# DMC.net
KiCad netlist of a schematic drawn in Altium Designer
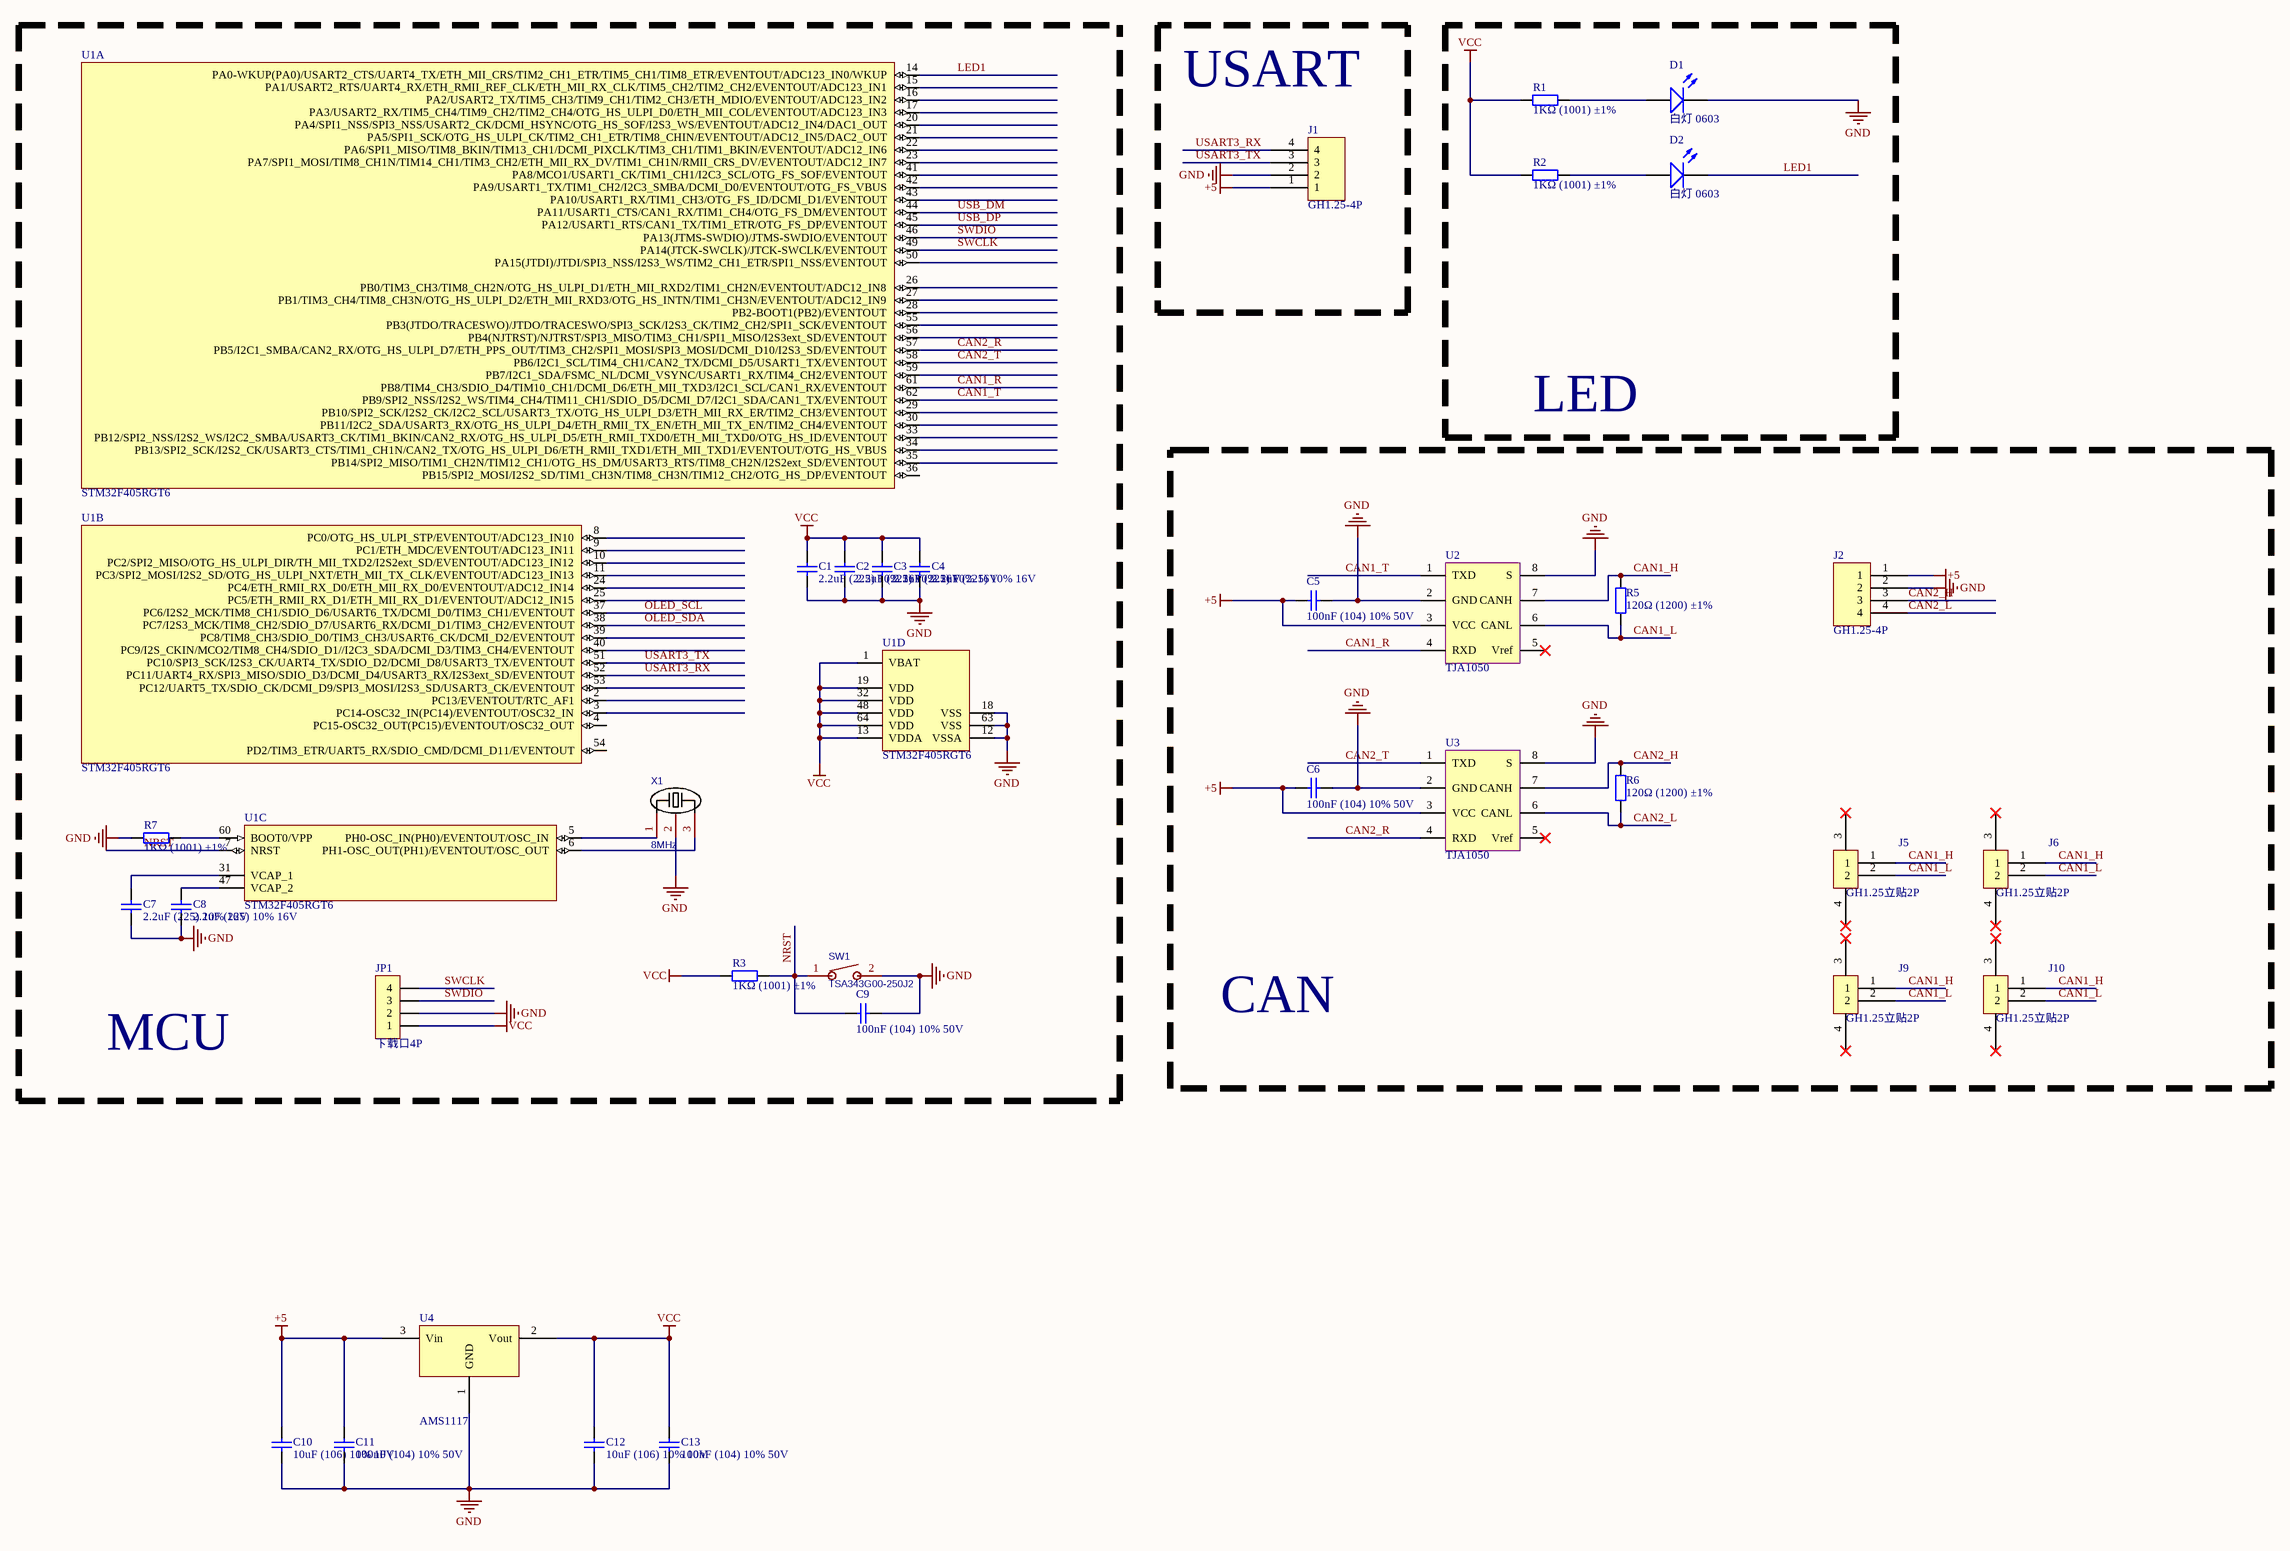
[diagram p0: DMC.SchDoc]

(export (version "E")
  (design (tool "Eeschema 10.0.6"))
  (components
    (comp (ref "C1")
      (value "2.2uF (225) 10% 16V")
      (footprint "0603_C")
      (description "贴片电容")
      (libsource (lib "Miscellaneous Devices LC") (part "0603 2.2uF (225) 10% 16V"))
    )
    (comp (ref "C2")
      (value "2.2uF (225) 10% 16V")
      (footprint "0603_C")
      (description "贴片电容")
      (libsource (lib "Miscellaneous Devices LC") (part "0603 2.2uF (225) 10% 16V"))
    )
    (comp (ref "C3")
      (value "2.2uF (225) 10% 16V")
      (footprint "0603_C")
      (description "贴片电容")
      (libsource (lib "Miscellaneous Devices LC") (part "0603 2.2uF (225) 10% 16V"))
    )
    (comp (ref "C4")
      (value "2.2uF (225) 10% 16V")
      (footprint "0603_C")
      (description "贴片电容")
      (libsource (lib "Miscellaneous Devices LC") (part "0603 2.2uF (225) 10% 16V"))
    )
    (comp (ref "C5")
      (value "100nF (104) 10% 50V")
      (footprint "0603_C")
      (description "贴片电容")
      (libsource (lib "Miscellaneous Devices LC") (part "0603 100nF (104) 10% 50V"))
    )
    (comp (ref "C6")
      (value "100nF (104) 10% 50V")
      (footprint "0603_C")
      (description "贴片电容")
      (libsource (lib "Miscellaneous Devices LC") (part "0603 100nF (104) 10% 50V"))
    )
    (comp (ref "C7")
      (value "2.2uF (225) 10% 16V")
      (footprint "0603_C")
      (description "贴片电容")
      (libsource (lib "Miscellaneous Devices LC") (part "0603 2.2uF (225) 10% 16V"))
    )
    (comp (ref "C8")
      (value "2.2uF (225) 10% 16V")
      (footprint "0603_C")
      (description "贴片电容")
      (libsource (lib "Miscellaneous Devices LC") (part "0603 2.2uF (225) 10% 16V"))
    )
    (comp (ref "C9")
      (value "100nF (104) 10% 50V")
      (footprint "0603_C")
      (description "贴片电容")
      (libsource (lib "Miscellaneous Devices LC") (part "0603 100nF (104) 10% 50V"))
    )
    (comp (ref "C10")
      (value "10uF (106) 10% 10V")
      (footprint "0603_C")
      (description "贴片电容")
      (libsource (lib "Miscellaneous Devices LC") (part "0603 10uF (106) 10% 10V"))
    )
    (comp (ref "C11")
      (value "100nF (104) 10% 50V")
      (footprint "0603_C")
      (description "贴片电容")
      (libsource (lib "Miscellaneous Devices LC") (part "0603 100nF (104) 10% 50V"))
    )
    (comp (ref "C12")
      (value "10uF (106) 10% 10V")
      (footprint "0603_C")
      (description "贴片电容")
      (libsource (lib "Miscellaneous Devices LC") (part "0603 10uF (106) 10% 10V"))
    )
    (comp (ref "C13")
      (value "100nF (104) 10% 50V")
      (footprint "0603_C")
      (description "贴片电容")
      (libsource (lib "Miscellaneous Devices LC") (part "0603 100nF (104) 10% 50V"))
    )
    (comp (ref "D1")
      (value "白灯 0603")
      (footprint "0603_LED_S1")
      (description "发光二极管")
      (libsource (lib "Miscellaneous Devices LC") (part "0603 白灯"))
    )
    (comp (ref "D2")
      (value "白灯 0603")
      (footprint "0603_LED_S1")
      (description "发光二极管")
      (libsource (lib "Miscellaneous Devices LC") (part "0603 白灯"))
    )
    (comp (ref "J1")
      (value "GH1.25-4P")
      (footprint "GH1.25-4P")
      (description "GH1.25-4P 卧")
      (libsource (lib "") (part "GH1.25-4P_1"))
    )
    (comp (ref "J2")
      (value "GH1.25-4P")
      (footprint "GH1.25-4P")
      (description "GH1.25-4P 卧")
      (libsource (lib "MyLib") (part "GH1.25-4P"))
    )
    (comp (ref "J5")
      (value "GH1.25立贴2P")
      (footprint "CONN-SMD_2P-V-P1.25-L_X1251WVS-02HF-LPSW")
      (libsource (lib "MyLib") (part "GH1.25立贴2P"))
    )
    (comp (ref "J6")
      (value "GH1.25立贴2P")
      (footprint "CONN-SMD_2P-V-P1.25-L_X1251WVS-02HF-LPSW")
      (libsource (lib "MyLib") (part "GH1.25立贴2P"))
    )
    (comp (ref "J9")
      (value "GH1.25立贴2P")
      (footprint "CONN-SMD_2P-V-P1.25-L_X1251WVS-02HF-LPSW")
      (libsource (lib "MyLib") (part "GH1.25立贴2P"))
    )
    (comp (ref "J10")
      (value "GH1.25立贴2P")
      (footprint "CONN-SMD_2P-V-P1.25-L_X1251WVS-02HF-LPSW")
      (libsource (lib "MyLib") (part "GH1.25立贴2P"))
    )
    (comp (ref "JP1")
      (value "下载口4P")
      (footprint "下载口4pin")
      (description "下载口4PIN SWD")
      (libsource (lib "0.0 - YltsSchlib") (part "接插件-下载口4P"))
    )
    (comp (ref "R1")
      (value "1KΩ (1001) ±1%")
      (footprint "0603_R")
      (description "贴片电阻")
      (libsource (lib "Miscellaneous Devices LC") (part "0603 1KΩ (1001) 1%"))
    )
    (comp (ref "R2")
      (value "1KΩ (1001) ±1%")
      (footprint "0603_R")
      (description "贴片电阻")
      (libsource (lib "Miscellaneous Devices LC") (part "0603 1KΩ (1001) 1%"))
    )
    (comp (ref "R3")
      (value "1KΩ (1001) ±1%")
      (footprint "0603_R")
      (description "贴片电阻")
      (libsource (lib "Miscellaneous Devices LC") (part "0603 1KΩ (1001) 1%"))
    )
    (comp (ref "R5")
      (value "120Ω (1200) ±1%")
      (footprint "0603_R")
      (description "贴片电阻")
      (libsource (lib "Miscellaneous Devices LC") (part "0603 120Ω (1200) 1%"))
    )
    (comp (ref "R6")
      (value "120Ω (1200) ±1%")
      (footprint "0603_R")
      (description "贴片电阻")
      (libsource (lib "Miscellaneous Devices LC") (part "0603 120Ω (1200) 1%"))
    )
    (comp (ref "R7")
      (value "1KΩ (1001) ±1%")
      (footprint "0603_R")
      (description "贴片电阻")
      (libsource (lib "Miscellaneous Devices LC") (part "0603 1KΩ (1001) 1%"))
    )
    (comp (ref "SW1")
      (value "TSA343G00-250J2")
      (footprint "SW-SMD_L4.0-W2.9-LS5.0")
      (description "贴片轻触开关")
      (fields (field (name "BOM_SUPPLIER PART") "C354946") (field (name "CONTRIBUTOR") "LCSC"))
      (libsource (lib "MyLib") (part "TSA343G00-250J2"))
    )
    (comp (ref "U1")
      (value "STM32F405RGT6")
      (footprint "TQFP64_M")
      (libsource (lib "MyLib") (part "STM32F405RGT6"))
    )
    (comp (ref "U2")
      (value "TJA1050")
      (footprint "SOIC-8_L5.0-W4.0-P1.27-LS6.0-BL")
      (libsource (lib "未分类IC") (part "TJA1050"))
    )
    (comp (ref "U3")
      (value "TJA1050")
      (footprint "SOIC-8_L5.0-W4.0-P1.27-LS6.0-BL")
      (libsource (lib "未分类IC") (part "TJA1050"))
    )
    (comp (ref "U4")
      (value "AMS1117")
      (footprint "SOT-223_L6.7-W3.5-P2.30-BR")
      (libsource (lib "MyLib") (part "AMS1117"))
    )
    (comp (ref "X1")
      (value "8MHz")
      (footprint "OSC-SMD_3P-L3.2-W1.3-P1.2-L")
      (fields
        (field (name "BOM_MANUFACTURER PART") "CSTCE8M00G15C99-R0")
        (field (name "BOM_SUPPLIER PART") "C110614")
      )
      (libsource (lib "MyLib") (part "8MHz-3P"))
    )
  )
  (nets
    (net (code "1") (name "+5") (class "Default")
      (node (ref "C10") (pin "2") (pinfunction "2_2") (pintype "passive"))
      (node (ref "C11") (pin "1") (pinfunction "1_1") (pintype "passive"))
      (node (ref "C5") (pin "2") (pinfunction "2_2") (pintype "passive"))
      (node (ref "C6") (pin "2") (pinfunction "2_2") (pintype "passive"))
      (node (ref "J1") (pin "1") (pinfunction "1_1") (pintype "passive"))
      (node (ref "J2") (pin "1") (pinfunction "1_1") (pintype "passive"))
      (node (ref "U2") (pin "3") (pinfunction "VCC_3") (pintype "passive"))
      (node (ref "U3") (pin "3") (pinfunction "VCC_3") (pintype "passive"))
      (node (ref "U4") (pin "3") (pinfunction "Vin_3") (pintype "passive"))
    )
    (net (code "2") (name "/CAN1_H") (class "Default")
      (node (ref "J10") (pin "1") (pinfunction "1_1") (pintype "passive"))
      (node (ref "J5") (pin "1") (pinfunction "1_1") (pintype "passive"))
      (node (ref "J6") (pin "1") (pinfunction "1_1") (pintype "passive"))
      (node (ref "J9") (pin "1") (pinfunction "1_1") (pintype "passive"))
      (node (ref "R5") (pin "2") (pinfunction "2_2") (pintype "passive"))
      (node (ref "U2") (pin "7") (pinfunction "CANH_7") (pintype "passive"))
    )
    (net (code "3") (name "/CAN1_L") (class "Default")
      (node (ref "J10") (pin "2") (pinfunction "2_2") (pintype "passive"))
      (node (ref "J5") (pin "2") (pinfunction "2_2") (pintype "passive"))
      (node (ref "J6") (pin "2") (pinfunction "2_2") (pintype "passive"))
      (node (ref "J9") (pin "2") (pinfunction "2_2") (pintype "passive"))
      (node (ref "R5") (pin "1") (pinfunction "1_1") (pintype "passive"))
      (node (ref "U2") (pin "6") (pinfunction "CANL_6") (pintype "passive"))
    )
    (net (code "4") (name "/CAN1_R") (class "Default")
      (node (ref "U1") (pin "61") (pinfunction "PB8/TIM4_CH3/SDIO_D4/TIM10_CH1/DCMI_D6/ETH_MII_TXD3/I2C1_SCL/CAN1_RX/EVENTOUT_61") (pintype "bidirectional"))
      (node (ref "U2") (pin "4") (pinfunction "RXD_4") (pintype "passive"))
    )
    (net (code "5") (name "/CAN1_T") (class "Default")
      (node (ref "U1") (pin "62") (pinfunction "PB9/SPI2_NSS/I2S2_WS/TIM4_CH4/TIM11_CH1/SDIO_D5/DCMI_D7/I2C1_SDA/CAN1_TX/EVENTOUT_62") (pintype "bidirectional"))
      (node (ref "U2") (pin "1") (pinfunction "TXD_1") (pintype "passive"))
    )
    (net (code "6") (name "/CAN2_H") (class "Default")
      (node (ref "J2") (pin "3") (pinfunction "3_3") (pintype "passive"))
      (node (ref "R6") (pin "2") (pinfunction "2_2") (pintype "passive"))
      (node (ref "U3") (pin "7") (pinfunction "CANH_7") (pintype "passive"))
    )
    (net (code "7") (name "/CAN2_L") (class "Default")
      (node (ref "J2") (pin "4") (pinfunction "4_4") (pintype "passive"))
      (node (ref "R6") (pin "1") (pinfunction "1_1") (pintype "passive"))
      (node (ref "U3") (pin "6") (pinfunction "CANL_6") (pintype "passive"))
    )
    (net (code "8") (name "/CAN2_R") (class "Default")
      (node (ref "U1") (pin "57") (pinfunction "PB5/I2C1_SMBA/CAN2_RX/OTG_HS_ULPI_D7/ETH_PPS_OUT/TIM3_CH2/SPI1_MOSI/SPI3_MOSI/DCMI_D10/I2S3_SD/EVENTOUT_57") (pintype "bidirectional"))
      (node (ref "U3") (pin "4") (pinfunction "RXD_4") (pintype "passive"))
    )
    (net (code "9") (name "/CAN2_T") (class "Default")
      (node (ref "U1") (pin "58") (pinfunction "PB6/I2C1_SCL/TIM4_CH1/CAN2_TX/DCMI_D5/USART1_TX/EVENTOUT_58") (pintype "bidirectional"))
      (node (ref "U3") (pin "1") (pinfunction "TXD_1") (pintype "passive"))
    )
    (net (code "10") (name "/LED1") (class "Default")
      (node (ref "D2") (pin "K") (pinfunction "K_K") (pintype "passive"))
      (node (ref "U1") (pin "14") (pinfunction "PA0-WKUP(PA0)/USART2_CTS/UART4_TX/ETH_MII_CRS/TIM2_CH1_ETR/TIM5_CH1/TIM8_ETR/EVENTOUT/ADC123_IN0/WKUP_14") (pintype "bidirectional"))
    )
    (net (code "11") (name "/NRST") (class "Default")
      (node (ref "C9") (pin "2") (pinfunction "2_2") (pintype "passive"))
      (node (ref "R3") (pin "2") (pinfunction "2_2") (pintype "passive"))
      (node (ref "SW1") (pin "1") (pinfunction "1_1") (pintype "passive"))
      (node (ref "U1") (pin "7") (pinfunction "NRST_7") (pintype "bidirectional"))
    )
    (net (code "12") (name "/OLED_SCL") (class "Default")
      (node (ref "U1") (pin "37") (pinfunction "PC6/I2S2_MCK/TIM8_CH1/SDIO_D6/USART6_TX/DCMI_D0/TIM3_CH1/EVENTOUT_37") (pintype "bidirectional"))
    )
    (net (code "13") (name "/OLED_SDA") (class "Default")
      (node (ref "U1") (pin "38") (pinfunction "PC7/I2S3_MCK/TIM8_CH2/SDIO_D7/USART6_RX/DCMI_D1/TIM3_CH2/EVENTOUT_38") (pintype "bidirectional"))
    )
    (net (code "14") (name "/SWCLK") (class "Default")
      (node (ref "JP1") (pin "4") (pinfunction "4_4") (pintype "passive"))
      (node (ref "U1") (pin "49") (pinfunction "PA14(JTCK-SWCLK)/JTCK-SWCLK/EVENTOUT_49") (pintype "bidirectional"))
    )
    (net (code "15") (name "/SWDIO") (class "Default")
      (node (ref "JP1") (pin "3") (pinfunction "3_3") (pintype "passive"))
      (node (ref "U1") (pin "46") (pinfunction "PA13(JTMS-SWDIO)/JTMS-SWDIO/EVENTOUT_46") (pintype "bidirectional"))
    )
    (net (code "16") (name "/USART3_RX") (class "Default")
      (node (ref "J1") (pin "4") (pinfunction "4_4") (pintype "passive"))
      (node (ref "U1") (pin "52") (pinfunction "PC11/UART4_RX/SPI3_MISO/SDIO_D3/DCMI_D4/USART3_RX/I2S3ext_SD/EVENTOUT_52") (pintype "bidirectional"))
    )
    (net (code "17") (name "/USART3_TX") (class "Default")
      (node (ref "J1") (pin "3") (pinfunction "3_3") (pintype "passive"))
      (node (ref "U1") (pin "51") (pinfunction "PC10/SPI3_SCK/I2S3_CK/UART4_TX/SDIO_D2/DCMI_D8/USART3_TX/EVENTOUT_51") (pintype "bidirectional"))
    )
    (net (code "18") (name "/USB_DM") (class "Default")
      (node (ref "U1") (pin "44") (pinfunction "PA11/USART1_CTS/CAN1_RX/TIM1_CH4/OTG_FS_DM/EVENTOUT_44") (pintype "bidirectional"))
    )
    (net (code "19") (name "/USB_DP") (class "Default")
      (node (ref "U1") (pin "45") (pinfunction "PA12/USART1_RTS/CAN1_TX/TIM1_ETR/OTG_FS_DP/EVENTOUT_45") (pintype "bidirectional"))
    )
    (net (code "20") (name "GND") (class "Default")
      (node (ref "C1") (pin "1") (pinfunction "1_1") (pintype "passive"))
      (node (ref "C10") (pin "1") (pinfunction "1_1") (pintype "passive"))
      (node (ref "C11") (pin "2") (pinfunction "2_2") (pintype "passive"))
      (node (ref "C12") (pin "1") (pinfunction "1_1") (pintype "passive"))
      (node (ref "C13") (pin "2") (pinfunction "2_2") (pintype "passive"))
      (node (ref "C2") (pin "1") (pinfunction "1_1") (pintype "passive"))
      (node (ref "C3") (pin "1") (pinfunction "1_1") (pintype "passive"))
      (node (ref "C4") (pin "1") (pinfunction "1_1") (pintype "passive"))
      (node (ref "C5") (pin "1") (pinfunction "1_1") (pintype "passive"))
      (node (ref "C6") (pin "1") (pinfunction "1_1") (pintype "passive"))
      (node (ref "C7") (pin "1") (pinfunction "1_1") (pintype "passive"))
      (node (ref "C8") (pin "1") (pinfunction "1_1") (pintype "passive"))
      (node (ref "C9") (pin "1") (pinfunction "1_1") (pintype "passive"))
      (node (ref "D1") (pin "K") (pinfunction "K_K") (pintype "passive"))
      (node (ref "J1") (pin "2") (pinfunction "2_2") (pintype "passive"))
      (node (ref "J2") (pin "2") (pinfunction "2_2") (pintype "passive"))
      (node (ref "JP1") (pin "2") (pinfunction "2_2") (pintype "passive"))
      (node (ref "R7") (pin "1") (pinfunction "1_1") (pintype "passive"))
      (node (ref "SW1") (pin "2") (pinfunction "2_2") (pintype "passive"))
      (node (ref "U1") (pin "12") (pinfunction "VSSA_12") (pintype "power_in"))
      (node (ref "U1") (pin "18") (pinfunction "VSS_18") (pintype "power_in"))
      (node (ref "U1") (pin "63") (pinfunction "VSS_63") (pintype "power_in"))
      (node (ref "U2") (pin "2") (pinfunction "GND_2") (pintype "passive"))
      (node (ref "U2") (pin "8") (pinfunction "S_8") (pintype "passive"))
      (node (ref "U3") (pin "2") (pinfunction "GND_2") (pintype "passive"))
      (node (ref "U3") (pin "8") (pinfunction "S_8") (pintype "passive"))
      (node (ref "U4") (pin "1") (pinfunction "GND_1") (pintype "passive"))
      (node (ref "X1") (pin "2") (pinfunction "2_2") (pintype "passive"))
    )
    (net (code "21") (name "Net-(D1-PadA)") (class "Default")
      (node (ref "D1") (pin "A") (pinfunction "A_A") (pintype "passive"))
      (node (ref "R1") (pin "2") (pinfunction "2_2") (pintype "passive"))
    )
    (net (code "22") (name "Net-(D2-PadA)") (class "Default")
      (node (ref "D2") (pin "A") (pinfunction "A_A") (pintype "passive"))
      (node (ref "R2") (pin "2") (pinfunction "2_2") (pintype "passive"))
    )
    (net (code "23") (name "Net-(U1C-BOOT0{slash}VPP)") (class "Default")
      (node (ref "R7") (pin "2") (pinfunction "2_2") (pintype "passive"))
      (node (ref "U1") (pin "60") (pinfunction "BOOT0/VPP_60") (pintype "input"))
    )
    (net (code "24") (name "Net-(U1C-PH0-OSC_IN(PH0){slash}EVENTOUT{slash}OSC_IN)") (class "Default")
      (node (ref "U1") (pin "5") (pinfunction "PH0-OSC_IN(PH0)/EVENTOUT/OSC_IN_5") (pintype "bidirectional"))
      (node (ref "X1") (pin "1") (pinfunction "1_1") (pintype "passive"))
    )
    (net (code "25") (name "Net-(U1C-PH1-OSC_OUT(PH1){slash}EVENTOUT{slash}OSC_OUT)") (class "Default")
      (node (ref "U1") (pin "6") (pinfunction "PH1-OSC_OUT(PH1)/EVENTOUT/OSC_OUT_6") (pintype "bidirectional"))
      (node (ref "X1") (pin "3") (pinfunction "3_3") (pintype "passive"))
    )
    (net (code "26") (name "Net-(U1C-VCAP_1)") (class "Default")
      (node (ref "C7") (pin "2") (pinfunction "2_2") (pintype "passive"))
      (node (ref "U1") (pin "31") (pinfunction "VCAP_1_31") (pintype "power_in"))
    )
    (net (code "27") (name "Net-(U1C-VCAP_2)") (class "Default")
      (node (ref "C8") (pin "2") (pinfunction "2_2") (pintype "passive"))
      (node (ref "U1") (pin "47") (pinfunction "VCAP_2_47") (pintype "power_in"))
    )
    (net (code "28") (name "VCC") (class "Default")
      (node (ref "C1") (pin "2") (pinfunction "2_2") (pintype "passive"))
      (node (ref "C12") (pin "2") (pinfunction "2_2") (pintype "passive"))
      (node (ref "C13") (pin "1") (pinfunction "1_1") (pintype "passive"))
      (node (ref "C2") (pin "2") (pinfunction "2_2") (pintype "passive"))
      (node (ref "C3") (pin "2") (pinfunction "2_2") (pintype "passive"))
      (node (ref "C4") (pin "2") (pinfunction "2_2") (pintype "passive"))
      (node (ref "JP1") (pin "1") (pinfunction "1_1") (pintype "passive"))
      (node (ref "R1") (pin "1") (pinfunction "1_1") (pintype "passive"))
      (node (ref "R2") (pin "1") (pinfunction "1_1") (pintype "passive"))
      (node (ref "R3") (pin "1") (pinfunction "1_1") (pintype "passive"))
      (node (ref "U1") (pin "1") (pinfunction "VBAT_1") (pintype "power_in"))
      (node (ref "U1") (pin "13") (pinfunction "VDDA_13") (pintype "power_in"))
      (node (ref "U1") (pin "19") (pinfunction "VDD_19") (pintype "power_in"))
      (node (ref "U1") (pin "32") (pinfunction "VDD_32") (pintype "power_in"))
      (node (ref "U1") (pin "48") (pinfunction "VDD_48") (pintype "power_in"))
      (node (ref "U1") (pin "64") (pinfunction "VDD_64") (pintype "power_in"))
      (node (ref "U4") (pin "2") (pinfunction "Vout_2") (pintype "passive"))
    )
    (net (code "29") (name "unconnected-(J5-Pad3)") (class "Default")
      (node (ref "J5") (pin "3") (pintype "passive+no_connect"))
    )
    (net (code "30") (name "unconnected-(J5-Pad4)") (class "Default")
      (node (ref "J5") (pin "4") (pintype "passive+no_connect"))
    )
    (net (code "31") (name "unconnected-(J6-Pad3)") (class "Default")
      (node (ref "J6") (pin "3") (pintype "passive+no_connect"))
    )
    (net (code "32") (name "unconnected-(J6-Pad4)") (class "Default")
      (node (ref "J6") (pin "4") (pintype "passive+no_connect"))
    )
    (net (code "33") (name "unconnected-(J9-Pad3)") (class "Default")
      (node (ref "J9") (pin "3") (pintype "passive+no_connect"))
    )
    (net (code "34") (name "unconnected-(J9-Pad4)") (class "Default")
      (node (ref "J9") (pin "4") (pintype "passive+no_connect"))
    )
    (net (code "35") (name "unconnected-(J10-Pad3)") (class "Default")
      (node (ref "J10") (pin "3") (pintype "passive+no_connect"))
    )
    (net (code "36") (name "unconnected-(J10-Pad4)") (class "Default")
      (node (ref "J10") (pin "4") (pintype "passive+no_connect"))
    )
    (net (code "37") (name "unconnected-(U1A-PA1{slash}USART2_RTS{slash}UART4_RX{slash}ETH_RMII_REF_CLK{slash}ETH_MII_RX_CLK{slash}TIM5_CH2{slash}TIM2_CH2{slash}EVENTOUT{slash}ADC123_IN1-Pad15)") (class "Default")
      (node (ref "U1") (pin "15") (pinfunction "PA1/USART2_RTS/UART4_RX/ETH_RMII_REF_CLK/ETH_MII_RX_CLK/TIM5_CH2/TIM2_CH2/EVENTOUT/ADC123_IN1_15") (pintype "bidirectional"))
    )
    (net (code "38") (name "unconnected-(U1A-PA2{slash}USART2_TX{slash}TIM5_CH3{slash}TIM9_CH1{slash}TIM2_CH3{slash}ETH_MDIO{slash}EVENTOUT{slash}ADC123_IN2-Pad16)") (class "Default")
      (node (ref "U1") (pin "16") (pinfunction "PA2/USART2_TX/TIM5_CH3/TIM9_CH1/TIM2_CH3/ETH_MDIO/EVENTOUT/ADC123_IN2_16") (pintype "bidirectional"))
    )
    (net (code "39") (name "unconnected-(U1A-PA3{slash}USART2_RX{slash}TIM5_CH4{slash}TIM9_CH2{slash}TIM2_CH4{slash}OTG_HS_ULPI_D0{slash}ETH_MII_COL{slash}EVENTOUT{slash}ADC123_IN3-Pad17)") (class "Default")
      (node (ref "U1") (pin "17") (pinfunction "PA3/USART2_RX/TIM5_CH4/TIM9_CH2/TIM2_CH4/OTG_HS_ULPI_D0/ETH_MII_COL/EVENTOUT/ADC123_IN3_17") (pintype "bidirectional"))
    )
    (net (code "40") (name "unconnected-(U1A-PA4{slash}SPI1_NSS{slash}SPI3_NSS{slash}USART2_CK{slash}DCMI_HSYNC{slash}OTG_HS_SOF{slash}I2S3_WS{slash}EVENTOUT{slash}ADC12_IN4{slash}DAC1_OUT-Pad20)") (class "Default")
      (node (ref "U1") (pin "20") (pinfunction "PA4/SPI1_NSS/SPI3_NSS/USART2_CK/DCMI_HSYNC/OTG_HS_SOF/I2S3_WS/EVENTOUT/ADC12_IN4/DAC1_OUT_20") (pintype "bidirectional"))
    )
    (net (code "41") (name "unconnected-(U1A-PA5{slash}SPI1_SCK{slash}OTG_HS_ULPI_CK{slash}TIM2_CH1_ETR{slash}TIM8_CHIN{slash}EVENTOUT{slash}ADC12_IN5{slash}DAC2_OUT-Pad21)") (class "Default")
      (node (ref "U1") (pin "21") (pinfunction "PA5/SPI1_SCK/OTG_HS_ULPI_CK/TIM2_CH1_ETR/TIM8_CHIN/EVENTOUT/ADC12_IN5/DAC2_OUT_21") (pintype "bidirectional"))
    )
    (net (code "42") (name "unconnected-(U1A-PA6{slash}SPI1_MISO{slash}TIM8_BKIN{slash}TIM13_CH1{slash}DCMI_PIXCLK{slash}TIM3_CH1{slash}TIM1_BKIN{slash}EVENTOUT{slash}ADC12_IN6-Pad22)") (class "Default")
      (node (ref "U1") (pin "22") (pinfunction "PA6/SPI1_MISO/TIM8_BKIN/TIM13_CH1/DCMI_PIXCLK/TIM3_CH1/TIM1_BKIN/EVENTOUT/ADC12_IN6_22") (pintype "bidirectional"))
    )
    (net (code "43") (name "unconnected-(U1A-PA7{slash}SPI1_MOSI{slash}TIM8_CH1N{slash}TIM14_CH1{slash}TIM3_CH2{slash}ETH_MII_RX_DV{slash}TIM1_CH1N{slash}RMII_CRS_DV{slash}EVENTOUT{slash}ADC12_IN7-Pad23)") (class "Default")
      (node (ref "U1") (pin "23") (pinfunction "PA7/SPI1_MOSI/TIM8_CH1N/TIM14_CH1/TIM3_CH2/ETH_MII_RX_DV/TIM1_CH1N/RMII_CRS_DV/EVENTOUT/ADC12_IN7_23") (pintype "bidirectional"))
    )
    (net (code "44") (name "unconnected-(U1A-PA8{slash}MCO1{slash}USART1_CK{slash}TIM1_CH1{slash}I2C3_SCL{slash}OTG_FS_SOF{slash}EVENTOUT-Pad41)") (class "Default")
      (node (ref "U1") (pin "41") (pinfunction "PA8/MCO1/USART1_CK/TIM1_CH1/I2C3_SCL/OTG_FS_SOF/EVENTOUT_41") (pintype "bidirectional"))
    )
    (net (code "45") (name "unconnected-(U1A-PA9{slash}USART1_TX{slash}TIM1_CH2{slash}I2C3_SMBA{slash}DCMI_D0{slash}EVENTOUT{slash}OTG_FS_VBUS-Pad42)") (class "Default")
      (node (ref "U1") (pin "42") (pinfunction "PA9/USART1_TX/TIM1_CH2/I2C3_SMBA/DCMI_D0/EVENTOUT/OTG_FS_VBUS_42") (pintype "bidirectional"))
    )
    (net (code "46") (name "unconnected-(U1A-PA10{slash}USART1_RX{slash}TIM1_CH3{slash}OTG_FS_ID{slash}DCMI_D1{slash}EVENTOUT-Pad43)") (class "Default")
      (node (ref "U1") (pin "43") (pinfunction "PA10/USART1_RX/TIM1_CH3/OTG_FS_ID/DCMI_D1/EVENTOUT_43") (pintype "bidirectional"))
    )
    (net (code "47") (name "unconnected-(U1A-PA15(JTDI){slash}JTDI{slash}SPI3_NSS{slash}I2S3_WS{slash}TIM2_CH1_ETR{slash}SPI1_NSS{slash}EVENTOUT-Pad50)") (class "Default")
      (node (ref "U1") (pin "50") (pinfunction "PA15(JTDI)/JTDI/SPI3_NSS/I2S3_WS/TIM2_CH1_ETR/SPI1_NSS/EVENTOUT_50") (pintype "bidirectional"))
    )
    (net (code "48") (name "unconnected-(U1A-PB0{slash}TIM3_CH3{slash}TIM8_CH2N{slash}OTG_HS_ULPI_D1{slash}ETH_MII_RXD2{slash}TIM1_CH2N{slash}EVENTOUT{slash}ADC12_IN8-Pad26)") (class "Default")
      (node (ref "U1") (pin "26") (pinfunction "PB0/TIM3_CH3/TIM8_CH2N/OTG_HS_ULPI_D1/ETH_MII_RXD2/TIM1_CH2N/EVENTOUT/ADC12_IN8_26") (pintype "bidirectional"))
    )
    (net (code "49") (name "unconnected-(U1A-PB1{slash}TIM3_CH4{slash}TIM8_CH3N{slash}OTG_HS_ULPI_D2{slash}ETH_MII_RXD3{slash}OTG_HS_INTN{slash}TIM1_CH3N{slash}EVENTOUT{slash}ADC12_IN9-Pad27)") (class "Default")
      (node (ref "U1") (pin "27") (pinfunction "PB1/TIM3_CH4/TIM8_CH3N/OTG_HS_ULPI_D2/ETH_MII_RXD3/OTG_HS_INTN/TIM1_CH3N/EVENTOUT/ADC12_IN9_27") (pintype "bidirectional"))
    )
    (net (code "50") (name "unconnected-(U1A-PB2-BOOT1(PB2){slash}EVENTOUT-Pad28)") (class "Default")
      (node (ref "U1") (pin "28") (pinfunction "PB2-BOOT1(PB2)/EVENTOUT_28") (pintype "bidirectional"))
    )
    (net (code "51") (name "unconnected-(U1A-PB3(JTDO{slash}TRACESWO){slash}JTDO{slash}TRACESWO{slash}SPI3_SCK{slash}I2S3_CK{slash}TIM2_CH2{slash}SPI1_SCK{slash}EVENTOUT-Pad55)") (class "Default")
      (node (ref "U1") (pin "55") (pinfunction "PB3(JTDO/TRACESWO)/JTDO/TRACESWO/SPI3_SCK/I2S3_CK/TIM2_CH2/SPI1_SCK/EVENTOUT_55") (pintype "bidirectional"))
    )
    (net (code "52") (name "unconnected-(U1A-PB4(NJTRST){slash}NJTRST{slash}SPI3_MISO{slash}TIM3_CH1{slash}SPI1_MISO{slash}I2S3ext_SD{slash}EVENTOUT-Pad56)") (class "Default")
      (node (ref "U1") (pin "56") (pinfunction "PB4(NJTRST)/NJTRST/SPI3_MISO/TIM3_CH1/SPI1_MISO/I2S3ext_SD/EVENTOUT_56") (pintype "bidirectional"))
    )
    (net (code "53") (name "unconnected-(U1A-PB7{slash}I2C1_SDA{slash}FSMC_NL{slash}DCMI_VSYNC{slash}USART1_RX{slash}TIM4_CH2{slash}EVENTOUT-Pad59)") (class "Default")
      (node (ref "U1") (pin "59") (pinfunction "PB7/I2C1_SDA/FSMC_NL/DCMI_VSYNC/USART1_RX/TIM4_CH2/EVENTOUT_59") (pintype "bidirectional"))
    )
    (net (code "54") (name "unconnected-(U1A-PB10{slash}SPI2_SCK{slash}I2S2_CK{slash}I2C2_SCL{slash}USART3_TX{slash}OTG_HS_ULPI_D3{slash}ETH_MII_RX_ER{slash}TIM2_CH3{slash}EVENTOUT-Pad29)") (class "Default")
      (node (ref "U1") (pin "29") (pinfunction "PB10/SPI2_SCK/I2S2_CK/I2C2_SCL/USART3_TX/OTG_HS_ULPI_D3/ETH_MII_RX_ER/TIM2_CH3/EVENTOUT_29") (pintype "bidirectional"))
    )
    (net (code "55") (name "unconnected-(U1A-PB11{slash}I2C2_SDA{slash}USART3_RX{slash}OTG_HS_ULPI_D4{slash}ETH_RMII_TX_EN{slash}ETH_MII_TX_EN{slash}TIM2_CH4{slash}EVENTOUT-Pad30)") (class "Default")
      (node (ref "U1") (pin "30") (pinfunction "PB11/I2C2_SDA/USART3_RX/OTG_HS_ULPI_D4/ETH_RMII_TX_EN/ETH_MII_TX_EN/TIM2_CH4/EVENTOUT_30") (pintype "bidirectional"))
    )
    (net (code "56") (name "unconnected-(U1A-PB12{slash}SPI2_NSS{slash}I2S2_WS{slash}I2C2_SMBA{slash}USART3_CK{slash}TIM1_BKIN{slash}CAN2_RX{slash}OTG_HS_ULPI_D5{slash}ETH_RMII_TXD0{slash}ETH_MII_TXD0{slash}OTG_HS_ID{slash}EVENTOUT-Pad33)") (class "Default")
      (node (ref "U1") (pin "33") (pinfunction "PB12/SPI2_NSS/I2S2_WS/I2C2_SMBA/USART3_CK/TIM1_BKIN/CAN2_RX/OTG_HS_ULPI_D5/ETH_RMII_TXD0/ETH_MII_TXD0/OTG_HS_ID/EVENTOUT_33") (pintype "bidirectional"))
    )
    (net (code "57") (name "unconnected-(U1A-PB13{slash}SPI2_SCK{slash}I2S2_CK{slash}USART3_CTS{slash}TIM1_CH1N{slash}CAN2_TX{slash}OTG_HS_ULPI_D6{slash}ETH_RMII_TXD1{slash}ETH_MII_TXD1{slash}EVENTOUT{slash}OTG_HS_VBUS-Pad34)") (class "Default")
      (node (ref "U1") (pin "34") (pinfunction "PB13/SPI2_SCK/I2S2_CK/USART3_CTS/TIM1_CH1N/CAN2_TX/OTG_HS_ULPI_D6/ETH_RMII_TXD1/ETH_MII_TXD1/EVENTOUT/OTG_HS_VBUS_34") (pintype "bidirectional"))
    )
    (net (code "58") (name "unconnected-(U1A-PB14{slash}SPI2_MISO{slash}TIM1_CH2N{slash}TIM12_CH1{slash}OTG_HS_DM{slash}USART3_RTS{slash}TIM8_CH2N{slash}I2S2ext_SD{slash}EVENTOUT-Pad35)") (class "Default")
      (node (ref "U1") (pin "35") (pinfunction "PB14/SPI2_MISO/TIM1_CH2N/TIM12_CH1/OTG_HS_DM/USART3_RTS/TIM8_CH2N/I2S2ext_SD/EVENTOUT_35") (pintype "bidirectional"))
    )
    (net (code "59") (name "unconnected-(U1A-PB15{slash}SPI2_MOSI{slash}I2S2_SD{slash}TIM1_CH3N{slash}TIM8_CH3N{slash}TIM12_CH2{slash}OTG_HS_DP{slash}EVENTOUT-Pad36)") (class "Default")
      (node (ref "U1") (pin "36") (pinfunction "PB15/SPI2_MOSI/I2S2_SD/TIM1_CH3N/TIM8_CH3N/TIM12_CH2/OTG_HS_DP/EVENTOUT_36") (pintype "bidirectional"))
    )
    (net (code "60") (name "unconnected-(U1B-PC0{slash}OTG_HS_ULPI_STP{slash}EVENTOUT{slash}ADC123_IN10-Pad8)") (class "Default")
      (node (ref "U1") (pin "8") (pinfunction "PC0/OTG_HS_ULPI_STP/EVENTOUT/ADC123_IN10_8") (pintype "bidirectional"))
    )
    (net (code "61") (name "unconnected-(U1B-PC1{slash}ETH_MDC{slash}EVENTOUT{slash}ADC123_IN11-Pad9)") (class "Default")
      (node (ref "U1") (pin "9") (pinfunction "PC1/ETH_MDC/EVENTOUT/ADC123_IN11_9") (pintype "bidirectional"))
    )
    (net (code "62") (name "unconnected-(U1B-PC2{slash}SPI2_MISO{slash}OTG_HS_ULPI_DIR{slash}TH_MII_TXD2{slash}I2S2ext_SD{slash}EVENTOUT{slash}ADC123_IN12-Pad10)") (class "Default")
      (node (ref "U1") (pin "10") (pinfunction "PC2/SPI2_MISO/OTG_HS_ULPI_DIR/TH_MII_TXD2/I2S2ext_SD/EVENTOUT/ADC123_IN12_10") (pintype "bidirectional"))
    )
    (net (code "63") (name "unconnected-(U1B-PC3{slash}SPI2_MOSI{slash}I2S2_SD{slash}OTG_HS_ULPI_NXT{slash}ETH_MII_TX_CLK{slash}EVENTOUT{slash}ADC123_IN13-Pad11)") (class "Default")
      (node (ref "U1") (pin "11") (pinfunction "PC3/SPI2_MOSI/I2S2_SD/OTG_HS_ULPI_NXT/ETH_MII_TX_CLK/EVENTOUT/ADC123_IN13_11") (pintype "bidirectional"))
    )
    (net (code "64") (name "unconnected-(U1B-PC4{slash}ETH_RMII_RX_D0{slash}ETH_MII_RX_D0{slash}EVENTOUT{slash}ADC12_IN14-Pad24)") (class "Default")
      (node (ref "U1") (pin "24") (pinfunction "PC4/ETH_RMII_RX_D0/ETH_MII_RX_D0/EVENTOUT/ADC12_IN14_24") (pintype "bidirectional"))
    )
    (net (code "65") (name "unconnected-(U1B-PC5{slash}ETH_RMII_RX_D1{slash}ETH_MII_RX_D1{slash}EVENTOUT{slash}ADC12_IN15-Pad25)") (class "Default")
      (node (ref "U1") (pin "25") (pinfunction "PC5/ETH_RMII_RX_D1/ETH_MII_RX_D1/EVENTOUT/ADC12_IN15_25") (pintype "bidirectional"))
    )
    (net (code "66") (name "unconnected-(U1B-PC8{slash}TIM8_CH3{slash}SDIO_D0{slash}TIM3_CH3{slash}USART6_CK{slash}DCMI_D2{slash}EVENTOUT-Pad39)") (class "Default")
      (node (ref "U1") (pin "39") (pinfunction "PC8/TIM8_CH3/SDIO_D0/TIM3_CH3/USART6_CK/DCMI_D2/EVENTOUT_39") (pintype "bidirectional"))
    )
    (net (code "67") (name "unconnected-(U1B-PC9{slash}I2S_CKIN{slash}MCO2{slash}TIM8_CH4{slash}SDIO_D1{slash}{slash}I2C3_SDA{slash}DCMI_D3{slash}TIM3_CH4{slash}EVENTOUT-Pad40)") (class "Default")
      (node (ref "U1") (pin "40") (pinfunction "PC9/I2S_CKIN/MCO2/TIM8_CH4/SDIO_D1//I2C3_SDA/DCMI_D3/TIM3_CH4/EVENTOUT_40") (pintype "bidirectional"))
    )
    (net (code "68") (name "unconnected-(U1B-PC12{slash}UART5_TX{slash}SDIO_CK{slash}DCMI_D9{slash}SPI3_MOSI{slash}I2S3_SD{slash}USART3_CK{slash}EVENTOUT-Pad53)") (class "Default")
      (node (ref "U1") (pin "53") (pinfunction "PC12/UART5_TX/SDIO_CK/DCMI_D9/SPI3_MOSI/I2S3_SD/USART3_CK/EVENTOUT_53") (pintype "bidirectional"))
    )
    (net (code "69") (name "unconnected-(U1B-PC13{slash}EVENTOUT{slash}RTC_AF1-Pad2)") (class "Default")
      (node (ref "U1") (pin "2") (pinfunction "PC13/EVENTOUT/RTC_AF1_2") (pintype "bidirectional"))
    )
    (net (code "70") (name "unconnected-(U1B-PC14-OSC32_IN(PC14){slash}EVENTOUT{slash}OSC32_IN-Pad3)") (class "Default")
      (node (ref "U1") (pin "3") (pinfunction "PC14-OSC32_IN(PC14)/EVENTOUT/OSC32_IN_3") (pintype "bidirectional"))
    )
    (net (code "71") (name "unconnected-(U1B-PC15-OSC32_OUT(PC15){slash}EVENTOUT{slash}OSC32_OUT-Pad4)") (class "Default")
      (node (ref "U1") (pin "4") (pinfunction "PC15-OSC32_OUT(PC15)/EVENTOUT/OSC32_OUT_4") (pintype "bidirectional"))
    )
    (net (code "72") (name "unconnected-(U1B-PD2{slash}TIM3_ETR{slash}UART5_RX{slash}SDIO_CMD{slash}DCMI_D11{slash}EVENTOUT-Pad54)") (class "Default")
      (node (ref "U1") (pin "54") (pinfunction "PD2/TIM3_ETR/UART5_RX/SDIO_CMD/DCMI_D11/EVENTOUT_54") (pintype "bidirectional"))
    )
    (net (code "73") (name "unconnected-(U2-Vref-Pad5)") (class "Default")
      (node (ref "U2") (pin "5") (pinfunction "Vref_5") (pintype "passive+no_connect"))
    )
    (net (code "74") (name "unconnected-(U3-Vref-Pad5)") (class "Default")
      (node (ref "U3") (pin "5") (pinfunction "Vref_5") (pintype "passive+no_connect"))
    )
  )
)
